# ft232h.net
KiCad netlist of a schematic drawn in Altium Designer
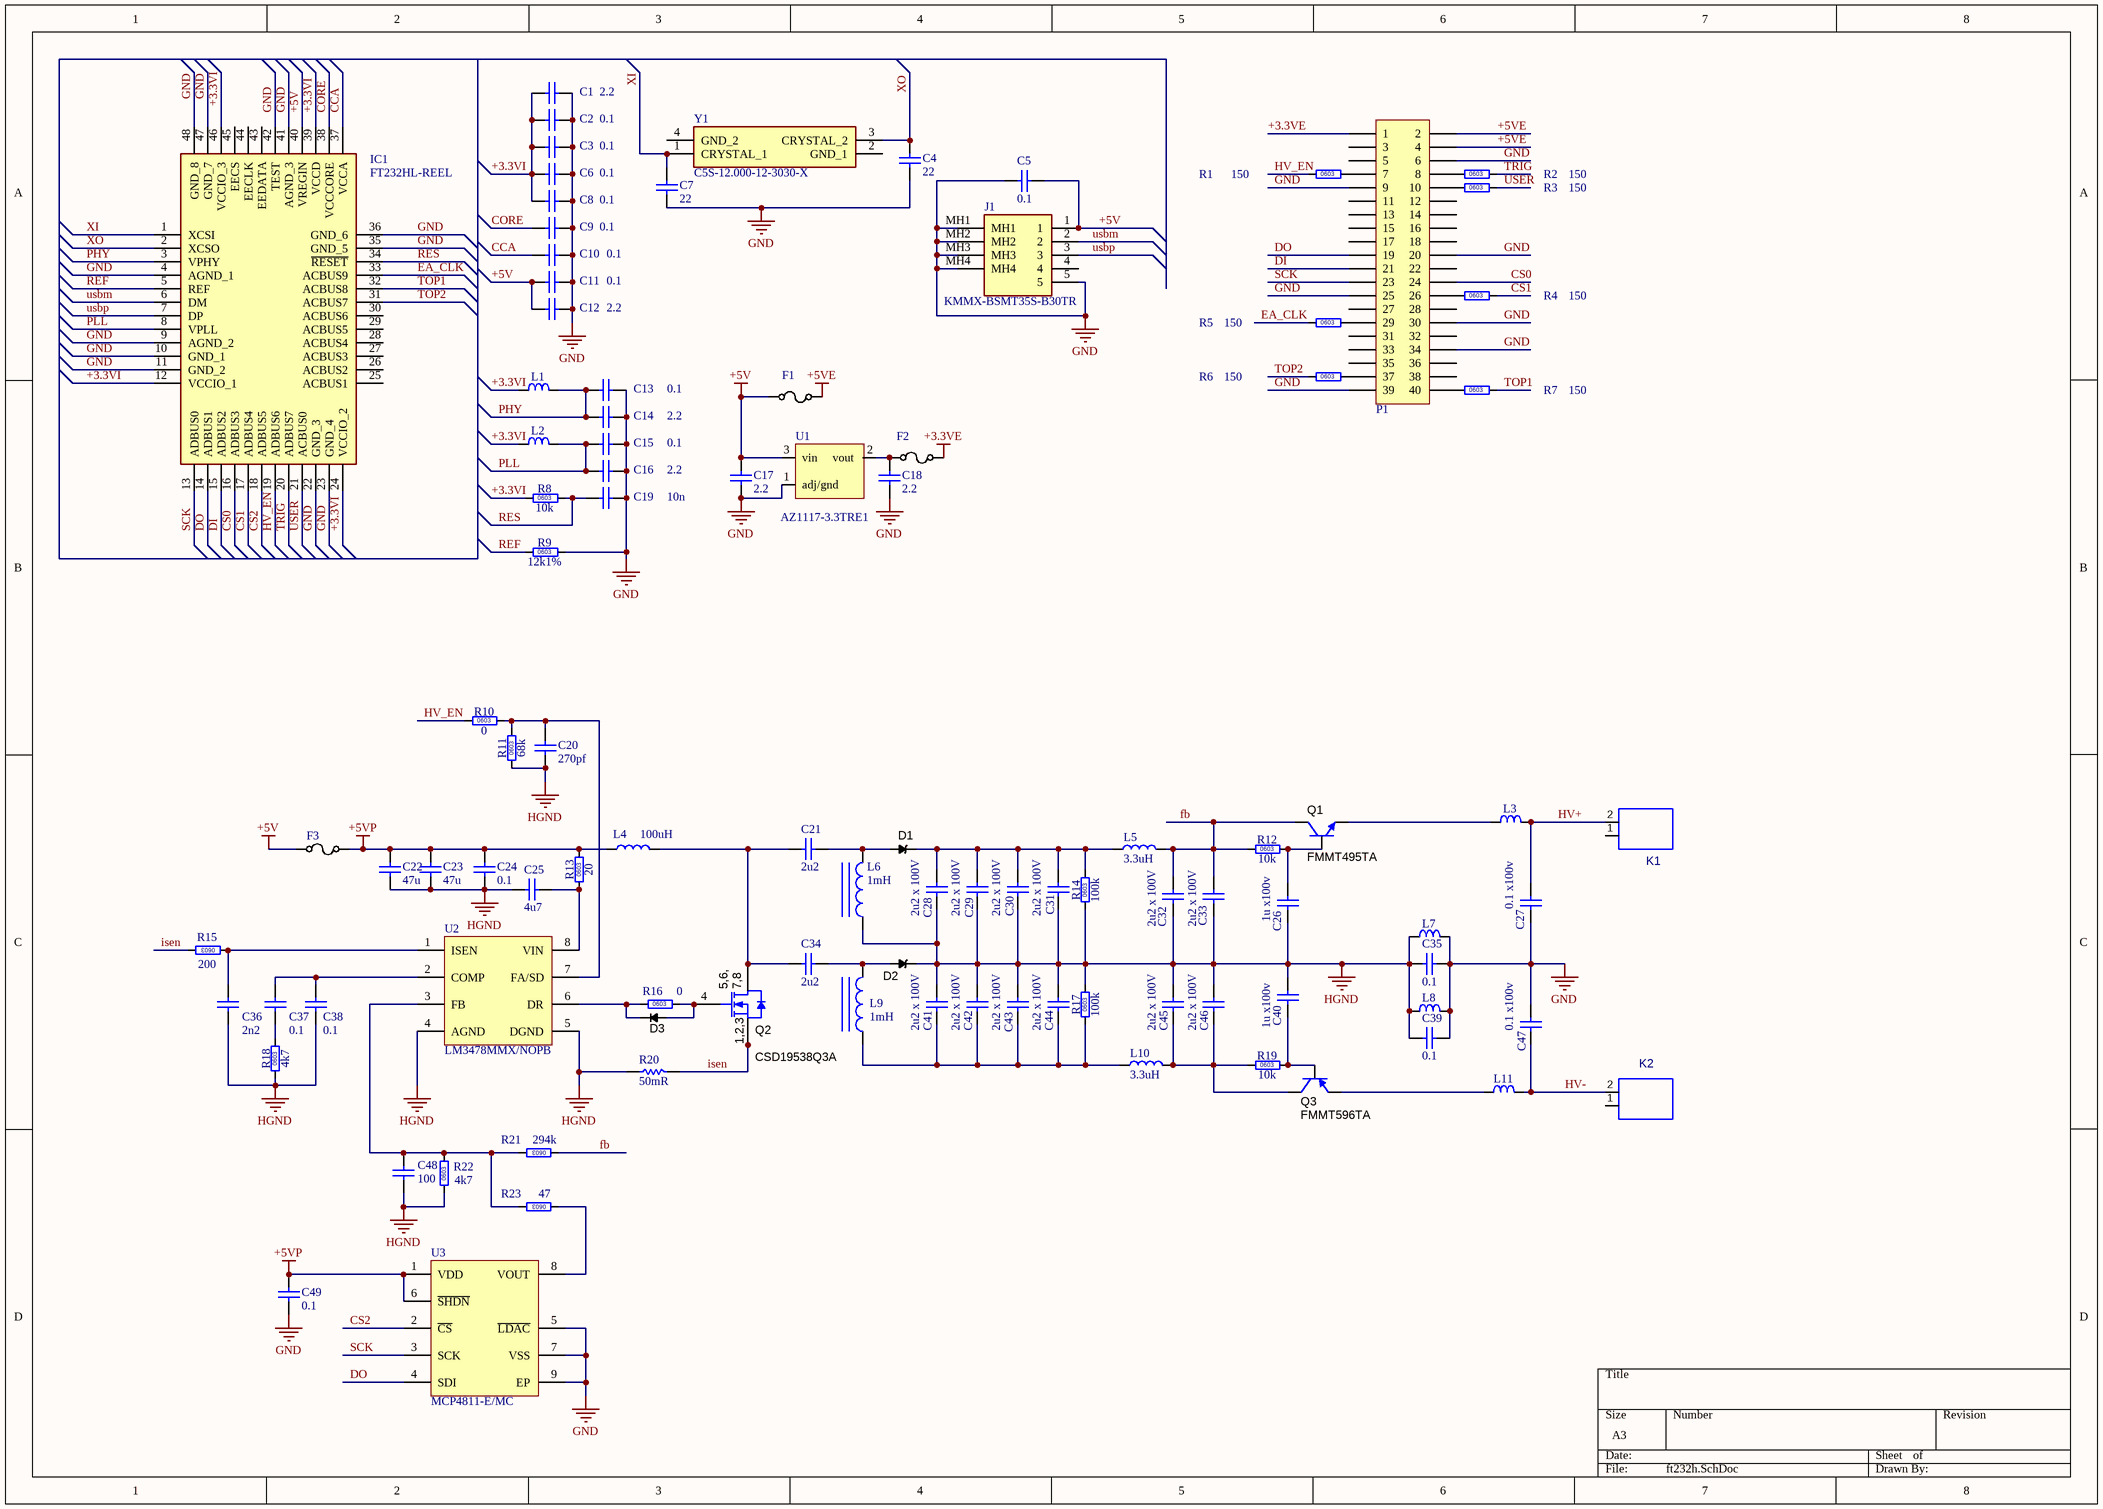
[diagram p0: ft232h.SchDoc]

(export (version "E")
  (design (tool "Eeschema 10.0.6"))
  (components
    (comp (ref "C1")
      (value "2.2")
      (footprint "SM0603 _3D_cap")
      (description "Capacitor  0603 inch")
      (fields (field (name "Comment") "cap0603"))
      (libsource (lib "alt2017") (part "cap0603"))
    )
    (comp (ref "C2")
      (value "0.1")
      (footprint "SM0603 _3D_cap")
      (description "Capacitor  0603 inch")
      (fields (field (name "Comment") "cap0603"))
      (libsource (lib "alt2017") (part "cap0603"))
    )
    (comp (ref "C3")
      (value "0.1")
      (footprint "SM0603 _3D_cap")
      (description "Capacitor  0603 inch")
      (fields (field (name "Comment") "cap0603"))
      (libsource (lib "alt2017") (part "cap0603"))
    )
    (comp (ref "C4")
      (value "22")
      (footprint "SM0603 _3D_cap")
      (description "Capacitor  0603 inch")
      (fields (field (name "Comment") "cap0603"))
      (libsource (lib "alt2017") (part "cap0603"))
    )
    (comp (ref "C5")
      (value "0.1")
      (footprint "SM0603 _3D_cap")
      (description "Capacitor  0603 inch")
      (fields (field (name "Comment") "cap0603"))
      (libsource (lib "alt2017") (part "cap0603"))
    )
    (comp (ref "C6")
      (value "0.1")
      (footprint "SM0603 _3D_cap")
      (description "Capacitor  0603 inch")
      (fields (field (name "Comment") "cap0603"))
      (libsource (lib "alt2017") (part "cap0603"))
    )
    (comp (ref "C7")
      (value "22")
      (footprint "SM0603 _3D_cap")
      (description "Capacitor  0603 inch")
      (fields (field (name "Comment") "cap0603"))
      (libsource (lib "alt2017") (part "cap0603"))
    )
    (comp (ref "C8")
      (value "0.1")
      (footprint "SM0603 _3D_cap")
      (description "Capacitor  0603 inch")
      (fields (field (name "Comment") "cap0603"))
      (libsource (lib "alt2017") (part "cap0603"))
    )
    (comp (ref "C9")
      (value "0.1")
      (footprint "SM0603 _3D_cap")
      (description "Capacitor  0603 inch")
      (fields (field (name "Comment") "cap0603"))
      (libsource (lib "alt2017") (part "cap0603"))
    )
    (comp (ref "C10")
      (value "0.1")
      (footprint "SM0603 _3D_cap")
      (description "Capacitor  0603 inch")
      (fields (field (name "Comment") "cap0603"))
      (libsource (lib "alt2017") (part "cap0603"))
    )
    (comp (ref "C11")
      (value "0.1")
      (footprint "SM0603 _3D_cap")
      (description "Capacitor  0603 inch")
      (fields (field (name "Comment") "cap0603"))
      (libsource (lib "alt2017") (part "cap0603"))
    )
    (comp (ref "C12")
      (value "2.2")
      (footprint "SM0603 _3D_cap")
      (description "Capacitor  0603 inch")
      (fields (field (name "Comment") "cap0603"))
      (libsource (lib "alt2017") (part "cap0603"))
    )
    (comp (ref "C13")
      (value "0.1")
      (footprint "SM0603 _3D_cap")
      (description "Capacitor  0603 inch")
      (fields (field (name "Comment") "cap0603"))
      (libsource (lib "alt2017") (part "cap0603"))
    )
    (comp (ref "C14")
      (value "2.2")
      (footprint "SM0603 _3D_cap")
      (description "Capacitor  0603 inch")
      (fields (field (name "Comment") "cap0603"))
      (libsource (lib "alt2017") (part "cap0603"))
    )
    (comp (ref "C15")
      (value "0.1")
      (footprint "SM0603 _3D_cap")
      (description "Capacitor  0603 inch")
      (fields (field (name "Comment") "cap0603"))
      (libsource (lib "alt2017") (part "cap0603"))
    )
    (comp (ref "C16")
      (value "2.2")
      (footprint "SM0603 _3D_cap")
      (description "Capacitor  0603 inch")
      (fields (field (name "Comment") "cap0603"))
      (libsource (lib "alt2017") (part "cap0603"))
    )
    (comp (ref "C17")
      (value "2.2")
      (footprint "SM0603 _3D_cap")
      (description "Capacitor  0603 inch")
      (fields (field (name "Comment") "cap0603"))
      (libsource (lib "alt2017") (part "cap0603"))
    )
    (comp (ref "C18")
      (value "2.2")
      (footprint "SM0603 _3D_cap")
      (description "Capacitor  0603 inch")
      (fields (field (name "Comment") "cap0603"))
      (libsource (lib "alt2017") (part "cap0603"))
    )
    (comp (ref "C19")
      (value "10n")
      (footprint "SM0603 _3D_cap")
      (description "Capacitor  0603 inch")
      (fields (field (name "Comment") "cap0603"))
      (libsource (lib "alt2017") (part "cap0603"))
    )
    (comp (ref "C20")
      (value "270pf")
      (footprint "SM0603 _3D_cap")
      (description "Capacitor  0603 inch")
      (fields (field (name "Comment") "cap0603"))
      (libsource (lib "alt2017") (part "cap0603"))
    )
    (comp (ref "C21")
      (value "2u2")
      (footprint "SM0603 _3D_cap")
      (description "Capacitor  0603 inch")
      (fields (field (name "Comment") "cap0603"))
      (libsource (lib "alt2017") (part "cap0603"))
    )
    (comp (ref "C22")
      (value "47u")
      (footprint "SM0805")
      (description "Capacitor")
      (fields (field (name "Comment") "cap0805"))
      (libsource (lib "alt2017") (part "cap0805"))
    )
    (comp (ref "C23")
      (value "47u")
      (footprint "SM0805")
      (description "Capacitor")
      (fields (field (name "Comment") "cap0805"))
      (libsource (lib "alt2017") (part "cap0805"))
    )
    (comp (ref "C24")
      (value "0.1")
      (footprint "SM0603 _3D_cap")
      (description "Capacitor  0603 inch")
      (fields (field (name "Comment") "cap0603"))
      (libsource (lib "alt2017") (part "cap0603"))
    )
    (comp (ref "C25")
      (value "4u7")
      (footprint "SM0603 _3D_cap")
      (description "Capacitor  0603 inch")
      (fields (field (name "Comment") "cap0603"))
      (libsource (lib "alt2017") (part "cap0603"))
    )
    (comp (ref "C26")
      (value "1u x100v")
      (footprint "SM0603 _3D_cap")
      (description "Capacitor  0603 inch")
      (fields (field (name "Comment") "cap0603"))
      (libsource (lib "alt2017") (part "cap0603"))
    )
    (comp (ref "C27")
      (value "0.1 x100v")
      (footprint "SM0603 _3D_cap")
      (description "Capacitor  0603 inch")
      (fields (field (name "Comment") "cap0603"))
      (libsource (lib "alt2017") (part "cap0603"))
    )
    (comp (ref "C28")
      (value "2u2 x 100V")
      (footprint "SM1206")
      (description "Capacitor")
      (fields (field (name "Comment") "cap1206"))
      (libsource (lib "alt2017") (part "cap1206"))
    )
    (comp (ref "C29")
      (value "2u2 x 100V")
      (footprint "SM1206")
      (description "Capacitor")
      (fields (field (name "Comment") "cap1206"))
      (libsource (lib "alt2017") (part "cap1206"))
    )
    (comp (ref "C30")
      (value "2u2 x 100V")
      (footprint "SM1206")
      (description "Capacitor")
      (fields (field (name "Comment") "cap1206"))
      (libsource (lib "alt2017") (part "cap1206"))
    )
    (comp (ref "C31")
      (value "2u2 x 100V")
      (footprint "SM1206")
      (description "Capacitor")
      (fields (field (name "Comment") "cap1206"))
      (libsource (lib "alt2017") (part "cap1206"))
    )
    (comp (ref "C32")
      (value "2u2 x 100V")
      (footprint "SM1206")
      (description "Capacitor")
      (fields (field (name "Comment") "cap1206"))
      (libsource (lib "alt2017") (part "cap1206"))
    )
    (comp (ref "C33")
      (value "2u2 x 100V")
      (footprint "SM1206")
      (description "Capacitor")
      (fields (field (name "Comment") "cap1206"))
      (libsource (lib "alt2017") (part "cap1206"))
    )
    (comp (ref "C34")
      (value "2u2")
      (footprint "SM0603 _3D_cap")
      (description "Capacitor  0603 inch")
      (fields (field (name "Comment") "cap0603"))
      (libsource (lib "alt2017") (part "cap0603"))
    )
    (comp (ref "C35")
      (value "0.1")
      (footprint "SM0603 _3D_cap")
      (description "Capacitor  0603 inch")
      (fields (field (name "Comment") "cap0603"))
      (libsource (lib "alt2017") (part "cap0603"))
    )
    (comp (ref "C36")
      (value "2n2")
      (footprint "SM0603 _3D_cap")
      (description "Capacitor  0603 inch")
      (fields (field (name "Comment") "cap0603"))
      (libsource (lib "alt2017") (part "cap0603"))
    )
    (comp (ref "C37")
      (value "0.1")
      (footprint "SM0603 _3D_cap")
      (description "Capacitor  0603 inch")
      (fields (field (name "Comment") "cap0603"))
      (libsource (lib "alt2017") (part "cap0603"))
    )
    (comp (ref "C38")
      (value "0.1")
      (footprint "SM0603 _3D_cap")
      (description "Capacitor  0603 inch")
      (fields (field (name "Comment") "cap0603"))
      (libsource (lib "alt2017") (part "cap0603"))
    )
    (comp (ref "C39")
      (value "0.1")
      (footprint "SM0603 _3D_cap")
      (description "Capacitor  0603 inch")
      (fields (field (name "Comment") "cap0603"))
      (libsource (lib "alt2017") (part "cap0603"))
    )
    (comp (ref "C40")
      (value "1u x100v")
      (footprint "SM0603 _3D_cap")
      (description "Capacitor  0603 inch")
      (fields (field (name "Comment") "cap0603"))
      (libsource (lib "alt2017") (part "cap0603"))
    )
    (comp (ref "C41")
      (value "2u2 x 100V")
      (footprint "SM1206")
      (description "Capacitor")
      (fields (field (name "Comment") "cap1206"))
      (libsource (lib "alt2017") (part "cap1206"))
    )
    (comp (ref "C42")
      (value "2u2 x 100V")
      (footprint "SM1206")
      (description "Capacitor")
      (fields (field (name "Comment") "cap1206"))
      (libsource (lib "alt2017") (part "cap1206"))
    )
    (comp (ref "C43")
      (value "2u2 x 100V")
      (footprint "SM1206")
      (description "Capacitor")
      (fields (field (name "Comment") "cap1206"))
      (libsource (lib "alt2017") (part "cap1206"))
    )
    (comp (ref "C44")
      (value "2u2 x 100V")
      (footprint "SM1206")
      (description "Capacitor")
      (fields (field (name "Comment") "cap1206"))
      (libsource (lib "alt2017") (part "cap1206"))
    )
    (comp (ref "C45")
      (value "2u2 x 100V")
      (footprint "SM1206")
      (description "Capacitor")
      (fields (field (name "Comment") "cap1206"))
      (libsource (lib "alt2017") (part "cap1206"))
    )
    (comp (ref "C46")
      (value "2u2 x 100V")
      (footprint "SM1206")
      (description "Capacitor")
      (fields (field (name "Comment") "cap1206"))
      (libsource (lib "alt2017") (part "cap1206"))
    )
    (comp (ref "C47")
      (value "0.1 x100v")
      (footprint "SM0603 _3D_cap")
      (description "Capacitor  0603 inch")
      (fields (field (name "Comment") "cap0603"))
      (libsource (lib "alt2017") (part "cap0603"))
    )
    (comp (ref "C48")
      (value "100")
      (footprint "SM0603 _3D_cap")
      (description "Capacitor  0603 inch")
      (fields (field (name "Comment") "cap0603"))
      (libsource (lib "alt2017") (part "cap0603"))
    )
    (comp (ref "C49")
      (value "0.1")
      (footprint "SM0603 _3D_cap")
      (description "Capacitor  0603 inch")
      (fields (field (name "Comment") "cap0603"))
      (libsource (lib "alt2017") (part "cap0603"))
    )
    (comp (ref "D1")
      (value "STPS1150A")
      (footprint "SMA")
      (description "DIODE SCHOTTKY 150V 1A SMA")
      (fields (field (name "MANUFACTURER") "STMicroelectronics"))
      (libsource (lib "alt2017") (part "STPS1150A"))
    )
    (comp (ref "D2")
      (value "STPS1150A")
      (footprint "SMA")
      (description "DIODE SCHOTTKY 150V 1A SMA")
      (fields (field (name "MANUFACTURER") "STMicroelectronics"))
      (libsource (lib "alt2017") (part "STPS1150A"))
    )
    (comp (ref "D3")
      (value "1N4148X-TP")
      (footprint "SOD-523")
      (description "DIODE SWITCHING 75V 0.3A SOD-523")
      (fields (field (name "MANUFACTURER") "Micro Commercial Components"))
      (libsource (lib "alt2017") (part "1N4148X-TP"))
    )
    (comp (ref "F1")
      (value "Fuse_0805")
      (footprint "MF-PSMF050X-2")
      (description "FUSE 0805 RESETTABLE PTC 6V 500MA")
      (fields
        (field (name "MANUFACTURER") "BOURNS")
        (field (name "MANUFACTURER PART NUMBER") "MF-PSMF050X-2")
      )
      (libsource (lib "alt2017") (part "Fuse_0805"))
    )
    (comp (ref "F2")
      (value "Fuse_0805")
      (footprint "MF-PSMF050X-2")
      (description "FUSE 0805 RESETTABLE PTC 6V 500MA")
      (fields
        (field (name "MANUFACTURER") "BOURNS")
        (field (name "MANUFACTURER PART NUMBER") "MF-PSMF050X-2")
      )
      (libsource (lib "alt2017") (part "Fuse_0805"))
    )
    (comp (ref "F3")
      (value "Fuse_0805")
      (footprint "MF-PSMF050X-2")
      (description "FUSE 0805 RESETTABLE PTC 6V 500MA")
      (fields
        (field (name "MANUFACTURER") "BOURNS")
        (field (name "MANUFACTURER PART NUMBER") "MF-PSMF050X-2")
      )
      (libsource (lib "alt2017") (part "Fuse_0805"))
    )
    (comp (ref "IC1")
      (value "FT232HL-REEL")
      (footprint "SamacSys:QFP50P900X900X160-48N")
      (description "Integrated Circuit")
      (fields (field (name "MOUSER PART NUMBER") "895-FT232HL-REEL"))
      (libsource (lib "*") (part "FT232HL-REEL"))
    )
    (comp (ref "J1")
      (value "KMMX-BSMT35S-B30TR")
      (footprint "SamacSys:KMMXBSMT35SB30TR")
      (description "Connector")
      (libsource (lib "*") (part "KMMX-BSMT35S-B30TR"))
    )
    (comp (ref "K1") (value "1x2PLS") (footprint "JUMPER2") (libsource (lib "alt2017") (part "1x2PLS")))
    (comp (ref "K2") (value "1x2PLS") (footprint "JUMPER2") (libsource (lib "alt2017") (part "1x2PLS")))
    (comp (ref "L1")
      (value "75R@100MHz")
      (footprint "SM0603_3D_res")
      (description "chip inductance 0603")
      (fields (field (name "PART NUMBER") "IND0805_MURATA_BLM21BB750SN1D") (field (name "POWER") "700mA"))
      (libsource (lib "alt_vovan") (part "chip inductance 0603"))
    )
    (comp (ref "L2")
      (value "75R@100MHz")
      (footprint "SM0603_3D_res")
      (description "chip inductance 0603")
      (fields (field (name "PART NUMBER") "IND0805_MURATA_BLM21BB750SN1D") (field (name "POWER") "700mA"))
      (libsource (lib "alt_vovan") (part "chip inductance 0603"))
    )
    (comp (ref "L3")
      (value "75R@100MHz")
      (footprint "SM0603_3D_res")
      (description "chip inductance 0603")
      (fields (field (name "PART NUMBER") "IND0805_MURATA_BLM21BB750SN1D") (field (name "POWER") "700mA"))
      (libsource (lib "alt_vovan") (part "chip inductance 0603"))
    )
    (comp (ref "L4")
      (value "100uH")
      (footprint "WE-LQS_8040")
      (description "INDUCTOR 100uH 8040 1A 290mOhm")
      (fields
        (field (name "MANUFACTURER") "Wurth Electronics")
        (field (name "MANUFACTURER PART NUMBER") "74404084101")
      )
      (libsource (lib "alt2017") (part "inductance_8040"))
    )
    (comp (ref "L5")
      (value "3.3uH")
      (footprint "WE 74479775233")
      (description "INDUCTOR 3.3uH 0805 ±20%  1A")
      (fields
        (field (name "MANUFACTURER") "Wurth Electronics")
        (field (name "MANUFACTURER PART NUMBER") "74479775233")
      )
      (libsource (lib "alt2017") (part "Inductor_0805"))
    )
    (comp (ref "L6")
      (value "1mH")
      (footprint "WE-TPC_4828")
      (description "INDUCTOR 1mH ±30% 140mA")
      (fields
        (field (name "MANUFACTURER") "Wurth Electronics")
        (field (name "MANUFACTURER PART NUMBER") "744043102")
      )
      (libsource (lib "alt2017") (part "inductor_4828"))
    )
    (comp (ref "L7")
      (value "75R@100MHz")
      (footprint "SM0603_3D_res")
      (description "chip inductance 0603")
      (fields (field (name "PART NUMBER") "IND0805_MURATA_BLM21BB750SN1D") (field (name "POWER") "700mA"))
      (libsource (lib "alt_vovan") (part "chip inductance 0603"))
    )
    (comp (ref "L8")
      (value "75R@100MHz")
      (footprint "SM0603_3D_res")
      (description "chip inductance 0603")
      (fields (field (name "PART NUMBER") "IND0805_MURATA_BLM21BB750SN1D") (field (name "POWER") "700mA"))
      (libsource (lib "alt_vovan") (part "chip inductance 0603"))
    )
    (comp (ref "L9")
      (value "1mH")
      (footprint "WE-TPC_4828")
      (description "INDUCTOR 1mH ±30% 140mA")
      (fields
        (field (name "MANUFACTURER") "Wurth Electronics")
        (field (name "MANUFACTURER PART NUMBER") "744043102")
      )
      (libsource (lib "alt2017") (part "inductor_4828"))
    )
    (comp (ref "L10")
      (value "3.3uH")
      (footprint "WE 74479775233")
      (description "INDUCTOR 3.3uH 0805 ±20%  1A")
      (fields
        (field (name "MANUFACTURER") "Wurth Electronics")
        (field (name "MANUFACTURER PART NUMBER") "74479775233")
      )
      (libsource (lib "alt2017") (part "Inductor_0805"))
    )
    (comp (ref "L11")
      (value "75R@100MHz")
      (footprint "SM0603_3D_res")
      (description "chip inductance 0603")
      (fields (field (name "PART NUMBER") "IND0805_MURATA_BLM21BB750SN1D") (field (name "POWER") "700mA"))
      (libsource (lib "alt_vovan") (part "chip inductance 0603"))
    )
    (comp (ref "P1")
      (value "2x20 2.54mm vertical")
      (footprint "PLD-40")
      (description "Header, 40-Pin")
      (libsource (lib "alt2017") (part "2x20 2.54mm vertical"))
    )
    (comp (ref "Q1")
      (value "FMMT495TA")
      (footprint "SOT-23-3")
      (description "TRANSISTOR NPN 150V 1A AEC-Q101 SOT-23")
      (fields (field (name "MANUFACTURER") "Diodes Inc."))
      (libsource (lib "alt2017") (part "FMMT495TA"))
    )
    (comp (ref "Q2")
      (value "CSD19538Q3A")
      (footprint "DNH0008A")
      (description "MOSFET N 100V 5A")
      (fields (field (name "MANUFACTURER") "Texas Instruments"))
      (libsource (lib "alt2017") (part "CSD19538Q3A"))
    )
    (comp (ref "Q3")
      (value "FMMT596TA")
      (footprint "SOT-23-3")
      (description "TRANSISTOR PNP 200V 0.3A SOT-23")
      (fields (field (name "MANUFACTURER") "Diodes Inc."))
      (libsource (lib "alt2017") (part "FMMT596TA"))
    )
    (comp (ref "R1")
      (value "150")
      (footprint "SM0603_3D_res")
      (description "Res_0603_EU")
      (fields (field (name "PART NUMBER") "R1206_4K7_1%_0.25W_100PPM") (field (name "POWER") "0.25W"))
      (libsource (lib "alt_vovan") (part "Res_0603_EU"))
    )
    (comp (ref "R2")
      (value "150")
      (footprint "SM0603_3D_res")
      (description "Res_0603_EU")
      (fields (field (name "PART NUMBER") "R1206_4K7_1%_0.25W_100PPM") (field (name "POWER") "0.25W"))
      (libsource (lib "alt_vovan") (part "Res_0603_EU"))
    )
    (comp (ref "R3")
      (value "150")
      (footprint "SM0603_3D_res")
      (description "Res_0603_EU")
      (fields (field (name "PART NUMBER") "R1206_4K7_1%_0.25W_100PPM") (field (name "POWER") "0.25W"))
      (libsource (lib "alt_vovan") (part "Res_0603_EU"))
    )
    (comp (ref "R4")
      (value "150")
      (footprint "SM0603_3D_res")
      (description "Res_0603_EU")
      (fields (field (name "PART NUMBER") "R1206_4K7_1%_0.25W_100PPM") (field (name "POWER") "0.25W"))
      (libsource (lib "alt_vovan") (part "Res_0603_EU"))
    )
    (comp (ref "R5")
      (value "150")
      (footprint "SM0603_3D_res")
      (description "Res_0603_EU")
      (fields (field (name "PART NUMBER") "R1206_4K7_1%_0.25W_100PPM") (field (name "POWER") "0.25W"))
      (libsource (lib "alt_vovan") (part "Res_0603_EU"))
    )
    (comp (ref "R6")
      (value "150")
      (footprint "SM0603_3D_res")
      (description "Res_0603_EU")
      (fields (field (name "PART NUMBER") "R1206_4K7_1%_0.25W_100PPM") (field (name "POWER") "0.25W"))
      (libsource (lib "alt_vovan") (part "Res_0603_EU"))
    )
    (comp (ref "R7")
      (value "150")
      (footprint "SM0603_3D_res")
      (description "Res_0603_EU")
      (fields (field (name "PART NUMBER") "R1206_4K7_1%_0.25W_100PPM") (field (name "POWER") "0.25W"))
      (libsource (lib "alt_vovan") (part "Res_0603_EU"))
    )
    (comp (ref "R8")
      (value "10k")
      (footprint "SM0603_3D_res")
      (description "Res_0603_EU")
      (fields (field (name "PART NUMBER") "R1206_4K7_1%_0.25W_100PPM") (field (name "POWER") "0.25W"))
      (libsource (lib "alt_vovan") (part "Res_0603_EU"))
    )
    (comp (ref "R9")
      (value "12k1%")
      (footprint "SM0603_3D_res")
      (description "Res_0603_EU")
      (fields (field (name "PART NUMBER") "R1206_4K7_1%_0.25W_100PPM") (field (name "POWER") "0.25W"))
      (libsource (lib "alt_vovan") (part "Res_0603_EU"))
    )
    (comp (ref "R10")
      (value "0")
      (footprint "SM0603_3D_res")
      (description "Res_0603_EU")
      (fields (field (name "PART NUMBER") "R1206_4K7_1%_0.25W_100PPM") (field (name "POWER") "0.25W"))
      (libsource (lib "alt_vovan") (part "Res_0603_EU"))
    )
    (comp (ref "R11")
      (value "68k")
      (footprint "SM0603_3D_res")
      (description "Res_0603_EU")
      (fields (field (name "PART NUMBER") "R1206_4K7_1%_0.25W_100PPM") (field (name "POWER") "0.25W"))
      (libsource (lib "alt_vovan") (part "Res_0603_EU"))
    )
    (comp (ref "R12")
      (value "10k")
      (footprint "SM0603_3D_res")
      (description "Res_0603_EU")
      (fields (field (name "PART NUMBER") "R1206_4K7_1%_0.25W_100PPM") (field (name "POWER") "0.25W"))
      (libsource (lib "alt_vovan") (part "Res_0603_EU"))
    )
    (comp (ref "R13")
      (value "20")
      (footprint "SM0603_3D_res")
      (description "Res_0603_EU")
      (fields (field (name "PART NUMBER") "R1206_4K7_1%_0.25W_100PPM") (field (name "POWER") "0.25W"))
      (libsource (lib "alt_vovan") (part "Res_0603_EU"))
    )
    (comp (ref "R14")
      (value "100k")
      (footprint "SM0603_3D_res")
      (description "Res_0603_EU")
      (fields (field (name "PART NUMBER") "R1206_4K7_1%_0.25W_100PPM") (field (name "POWER") "0.25W"))
      (libsource (lib "alt_vovan") (part "Res_0603_EU"))
    )
    (comp (ref "R15")
      (value "200")
      (footprint "SM0603_3D_res")
      (description "Res_0603_EU")
      (fields (field (name "PART NUMBER") "R1206_4K7_1%_0.25W_100PPM") (field (name "POWER") "0.25W"))
      (libsource (lib "alt_vovan") (part "Res_0603_EU"))
    )
    (comp (ref "R16")
      (value "0")
      (footprint "SM0603_3D_res")
      (description "Res_0603_EU")
      (fields (field (name "PART NUMBER") "R1206_4K7_1%_0.25W_100PPM") (field (name "POWER") "0.25W"))
      (libsource (lib "alt_vovan") (part "Res_0603_EU"))
    )
    (comp (ref "R17")
      (value "100k")
      (footprint "SM0603_3D_res")
      (description "Res_0603_EU")
      (fields (field (name "PART NUMBER") "R1206_4K7_1%_0.25W_100PPM") (field (name "POWER") "0.25W"))
      (libsource (lib "alt_vovan") (part "Res_0603_EU"))
    )
    (comp (ref "R18")
      (value "4k7")
      (footprint "SM0603_3D_res")
      (description "Res_0603_EU")
      (fields (field (name "PART NUMBER") "R1206_4K7_1%_0.25W_100PPM") (field (name "POWER") "0.25W"))
      (libsource (lib "alt_vovan") (part "Res_0603_EU"))
    )
    (comp (ref "R19")
      (value "10k")
      (footprint "SM0603_3D_res")
      (description "Res_0603_EU")
      (fields (field (name "PART NUMBER") "R1206_4K7_1%_0.25W_100PPM") (field (name "POWER") "0.25W"))
      (libsource (lib "alt_vovan") (part "Res_0603_EU"))
    )
    (comp (ref "R20")
      (value "50mR")
      (footprint "RES 2010/5025")
      (description "RESISTOR 0.05R 2010 1%")
      (fields
        (field (name "MANUFACTURER") "Panasonic")
        (field (name "MANUFACTURER PART NUMBER") "ERJ-L1DKF50MU")
      )
      (libsource (lib "alt2017") (part "Res_SMT_2010"))
    )
    (comp (ref "R21")
      (value "294k")
      (footprint "SM0603_3D_res")
      (description "Res_0603_EU")
      (fields (field (name "PART NUMBER") "R1206_4K7_1%_0.25W_100PPM") (field (name "POWER") "0.25W"))
      (libsource (lib "alt_vovan") (part "Res_0603_EU"))
    )
    (comp (ref "R22")
      (value "4k7")
      (footprint "SM0603_3D_res")
      (description "Res_0603_EU")
      (fields (field (name "PART NUMBER") "R1206_4K7_1%_0.25W_100PPM") (field (name "POWER") "0.25W"))
      (libsource (lib "alt_vovan") (part "Res_0603_EU"))
    )
    (comp (ref "R23")
      (value "47")
      (footprint "SM0603_3D_res")
      (description "Res_0603_EU")
      (fields (field (name "PART NUMBER") "R1206_4K7_1%_0.25W_100PPM") (field (name "POWER") "0.25W"))
      (libsource (lib "alt_vovan") (part "Res_0603_EU"))
    )
    (comp (ref "U1")
      (value "ldo")
      (footprint "SOT89-150P409X160-3N")
      (description "SOT89-3 ldo")
      (fields (field (name "ALTIUM_UNNAMED_1") "AZ1117-3.3TRE1"))
      (libsource (lib "alt2017") (part "LM1117-XX-SOT89-3"))
    )
    (comp (ref "U2")
      (value "LM3478MMX/NOPB")
      (footprint "MSOP8")
      (description "DC/DC Controller 2.97V to 40V Input")
      (fields (field (name "MANUFACTURER") "TI National Semiconductor"))
      (libsource (lib "alt_vovan") (part "LM3478MMX/NOPB"))
    )
    (comp (ref "U3")
      (value "MCP4811-E/MC")
      (footprint "DFN-8")
      (description "DAC 1-CH 10-bit DFN-8")
      (fields (field (name "MANUFACTURER") "Microchip"))
      (libsource (lib "alt2017") (part "MCP4811-E/MC"))
    )
    (comp (ref "Y1")
      (value "C5S-12.000-12-3030-X")
      (footprint "SamacSys:C5S")
      (description "Crystal or Oscillator")
      (libsource (lib "*") (part "C5S-12.000-12-3030-X"))
    )
  )
  (nets
    (net (code "1") (name "+3.3VE") (class "Default")
      (node (ref "F2") (pin "2") (pinfunction "2_2") (pintype "passive"))
      (node (ref "P1") (pin "1") (pinfunction "1_1") (pintype "passive"))
    )
    (net (code "2") (name "+5V") (class "Default")
      (node (ref "C11") (pin "2") (pinfunction "2_2") (pintype "passive"))
      (node (ref "C12") (pin "2") (pinfunction "2_2") (pintype "passive"))
      (node (ref "C17") (pin "2") (pinfunction "2_2") (pintype "passive"))
      (node (ref "C5") (pin "1") (pinfunction "1_1") (pintype "passive"))
      (node (ref "F1") (pin "1") (pinfunction "1_1") (pintype "passive"))
      (node (ref "F3") (pin "1") (pinfunction "1_1") (pintype "passive"))
      (node (ref "IC1") (pin "40") (pinfunction "VREGIN_40") (pintype "passive"))
      (node (ref "J1") (pin "1") (pinfunction "1_1") (pintype "passive"))
      (node (ref "U1") (pin "3") (pinfunction "vin_3") (pintype "passive"))
    )
    (net (code "3") (name "+5VE") (class "Default")
      (node (ref "F1") (pin "2") (pinfunction "2_2") (pintype "passive"))
      (node (ref "P1") (pin "2") (pinfunction "2_2") (pintype "passive"))
      (node (ref "P1") (pin "4") (pinfunction "4_4") (pintype "passive"))
    )
    (net (code "4") (name "+5VP") (class "Default")
      (node (ref "C22") (pin "2") (pinfunction "2_2") (pintype "passive"))
      (node (ref "C23") (pin "2") (pinfunction "2_2") (pintype "passive"))
      (node (ref "C24") (pin "2") (pinfunction "2_2") (pintype "passive"))
      (node (ref "C49") (pin "1") (pinfunction "1_1") (pintype "passive"))
      (node (ref "F3") (pin "2") (pinfunction "2_2") (pintype "passive"))
      (node (ref "L4") (pin "1") (pinfunction "1_1") (pintype "passive"))
      (node (ref "R13") (pin "2") (pinfunction "2_2") (pintype "passive"))
      (node (ref "U3") (pin "1") (pinfunction "VDD_1") (pintype "passive"))
      (node (ref "U3") (pin "6") (pinfunction "~{SHDN}_6") (pintype "passive"))
    )
    (net (code "5") (name "/+3.3VI") (class "Default")
      (node (ref "C1") (pin "2") (pinfunction "2_2") (pintype "passive"))
      (node (ref "C2") (pin "2") (pinfunction "2_2") (pintype "passive"))
      (node (ref "C3") (pin "2") (pinfunction "2_2") (pintype "passive"))
      (node (ref "C6") (pin "2") (pinfunction "2_2") (pintype "passive"))
      (node (ref "C8") (pin "2") (pinfunction "2_2") (pintype "passive"))
      (node (ref "IC1") (pin "12") (pinfunction "VCCIO_1_12") (pintype "passive"))
      (node (ref "IC1") (pin "24") (pinfunction "VCCIO_2_24") (pintype "passive"))
      (node (ref "IC1") (pin "39") (pinfunction "VCCD_39") (pintype "passive"))
      (node (ref "IC1") (pin "46") (pinfunction "VCCIO_3_46") (pintype "passive"))
      (node (ref "L1") (pin "1") (pinfunction "1_1") (pintype "passive"))
      (node (ref "L2") (pin "1") (pinfunction "1_1") (pintype "passive"))
      (node (ref "R8") (pin "1") (pinfunction "1_1") (pintype "passive"))
    )
    (net (code "6") (name "/CCA") (class "Default")
      (node (ref "C10") (pin "2") (pinfunction "2_2") (pintype "passive"))
      (node (ref "IC1") (pin "37") (pinfunction "VCCA_37") (pintype "passive"))
    )
    (net (code "7") (name "/CORE") (class "Default")
      (node (ref "C9") (pin "2") (pinfunction "2_2") (pintype "passive"))
      (node (ref "IC1") (pin "38") (pinfunction "VCCCORE_38") (pintype "passive"))
    )
    (net (code "8") (name "/CS0") (class "Default")
      (node (ref "IC1") (pin "16") (pinfunction "ADBUS3_16") (pintype "passive"))
      (node (ref "P1") (pin "24") (pinfunction "24_24") (pintype "passive"))
    )
    (net (code "9") (name "/CS1") (class "Default")
      (node (ref "IC1") (pin "17") (pinfunction "ADBUS4_17") (pintype "passive"))
      (node (ref "R4") (pin "2") (pinfunction "2_2") (pintype "passive"))
    )
    (net (code "10") (name "/CS2") (class "Default")
      (node (ref "IC1") (pin "18") (pinfunction "ADBUS5_18") (pintype "passive"))
      (node (ref "U3") (pin "2") (pinfunction "~{CS}_2") (pintype "passive"))
    )
    (net (code "11") (name "/DI") (class "Default")
      (node (ref "IC1") (pin "15") (pinfunction "ADBUS2_15") (pintype "passive"))
      (node (ref "P1") (pin "21") (pinfunction "21_21") (pintype "passive"))
    )
    (net (code "12") (name "/DO") (class "Default")
      (node (ref "IC1") (pin "14") (pinfunction "ADBUS1_14") (pintype "passive"))
      (node (ref "P1") (pin "19") (pinfunction "19_19") (pintype "passive"))
      (node (ref "U3") (pin "4") (pinfunction "SDI_4") (pintype "passive"))
    )
    (net (code "13") (name "/EA_CLK") (class "Default")
      (node (ref "IC1") (pin "33") (pinfunction "ACBUS9_33") (pintype "passive"))
      (node (ref "R5") (pin "1") (pinfunction "1_1") (pintype "passive"))
    )
    (net (code "14") (name "/HV+") (class "Default")
      (node (ref "C27") (pin "2") (pinfunction "2_2") (pintype "passive"))
      (node (ref "K1") (pin "2") (pinfunction "2_2") (pintype "passive"))
      (node (ref "L3") (pin "2") (pinfunction "2_2") (pintype "passive"))
    )
    (net (code "15") (name "/HV-") (class "Default")
      (node (ref "C47") (pin "1") (pinfunction "1_1") (pintype "passive"))
      (node (ref "K2") (pin "2") (pinfunction "2_2") (pintype "passive"))
      (node (ref "L11") (pin "2") (pinfunction "2_2") (pintype "passive"))
    )
    (net (code "16") (name "/HV_EN") (class "Default")
      (node (ref "IC1") (pin "19") (pinfunction "ADBUS6_19") (pintype "passive"))
      (node (ref "R1") (pin "1") (pinfunction "1_1") (pintype "passive"))
      (node (ref "R10") (pin "1") (pinfunction "1_1") (pintype "passive"))
    )
    (net (code "17") (name "/PHY") (class "Default")
      (node (ref "C13") (pin "2") (pinfunction "2_2") (pintype "passive"))
      (node (ref "C14") (pin "2") (pinfunction "2_2") (pintype "passive"))
      (node (ref "IC1") (pin "3") (pinfunction "VPHY_3") (pintype "passive"))
      (node (ref "L1") (pin "2") (pinfunction "2_2") (pintype "passive"))
    )
    (net (code "18") (name "/PLL") (class "Default")
      (node (ref "C15") (pin "2") (pinfunction "2_2") (pintype "passive"))
      (node (ref "C16") (pin "2") (pinfunction "2_2") (pintype "passive"))
      (node (ref "IC1") (pin "8") (pinfunction "VPLL_8") (pintype "passive"))
      (node (ref "L2") (pin "2") (pinfunction "2_2") (pintype "passive"))
    )
    (net (code "19") (name "/REF") (class "Default")
      (node (ref "IC1") (pin "5") (pinfunction "REF_5") (pintype "passive"))
      (node (ref "R9") (pin "1") (pinfunction "1_1") (pintype "passive"))
    )
    (net (code "20") (name "/RES") (class "Default")
      (node (ref "C19") (pin "2") (pinfunction "2_2") (pintype "passive"))
      (node (ref "IC1") (pin "34") (pinfunction "~{RESET}_34") (pintype "passive"))
      (node (ref "R8") (pin "2") (pinfunction "2_2") (pintype "passive"))
    )
    (net (code "21") (name "/SCK") (class "Default")
      (node (ref "IC1") (pin "13") (pinfunction "ADBUS0_13") (pintype "passive"))
      (node (ref "P1") (pin "23") (pinfunction "23_23") (pintype "passive"))
      (node (ref "U3") (pin "3") (pinfunction "SCK_3") (pintype "passive"))
    )
    (net (code "22") (name "/TOP1") (class "Default")
      (node (ref "IC1") (pin "32") (pinfunction "ACBUS8_32") (pintype "passive"))
      (node (ref "R7") (pin "2") (pinfunction "2_2") (pintype "passive"))
    )
    (net (code "23") (name "/TOP2") (class "Default")
      (node (ref "IC1") (pin "31") (pinfunction "ACBUS7_31") (pintype "passive"))
      (node (ref "R6") (pin "1") (pinfunction "1_1") (pintype "passive"))
    )
    (net (code "24") (name "/TRIG") (class "Default")
      (node (ref "IC1") (pin "20") (pinfunction "ADBUS7_20") (pintype "passive"))
      (node (ref "R2") (pin "2") (pinfunction "2_2") (pintype "passive"))
    )
    (net (code "25") (name "/USER") (class "Default")
      (node (ref "IC1") (pin "21") (pinfunction "ACBUS0_21") (pintype "passive"))
      (node (ref "R3") (pin "2") (pinfunction "2_2") (pintype "passive"))
    )
    (net (code "26") (name "/XI") (class "Default")
      (node (ref "C7") (pin "2") (pinfunction "2_2") (pintype "passive"))
      (node (ref "IC1") (pin "1") (pinfunction "XCSI_1") (pintype "passive"))
      (node (ref "Y1") (pin "1") (pinfunction "CRYSTAL_1_1") (pintype "passive"))
    )
    (net (code "27") (name "/XO") (class "Default")
      (node (ref "C4") (pin "2") (pinfunction "2_2") (pintype "passive"))
      (node (ref "IC1") (pin "2") (pinfunction "XCSO_2") (pintype "passive"))
      (node (ref "Y1") (pin "3") (pinfunction "CRYSTAL_2_3") (pintype "passive"))
    )
    (net (code "28") (name "/fb") (class "Default")
      (node (ref "C32") (pin "2") (pinfunction "2_2") (pintype "passive"))
      (node (ref "C33") (pin "2") (pinfunction "2_2") (pintype "passive"))
      (node (ref "L5") (pin "2") (pinfunction "2_2") (pintype "passive"))
      (node (ref "Q1") (pin "3") (pinfunction "C_3") (pintype "passive"))
      (node (ref "R12") (pin "1") (pinfunction "1_1") (pintype "passive"))
      (node (ref "R21") (pin "1") (pinfunction "1_1") (pintype "passive"))
    )
    (net (code "29") (name "/isen") (class "Default")
      (node (ref "Q2") (pin "1") (pinfunction "S_1") (pintype "passive"))
      (node (ref "Q2") (pin "2") (pinfunction "S_2") (pintype "passive"))
      (node (ref "Q2") (pin "3") (pinfunction "S_3") (pintype "passive"))
      (node (ref "R15") (pin "2") (pinfunction "2_2") (pintype "passive"))
      (node (ref "R20") (pin "2") (pintype "passive"))
    )
    (net (code "30") (name "/usbm") (class "Default")
      (node (ref "IC1") (pin "6") (pinfunction "DM_6") (pintype "passive"))
      (node (ref "J1") (pin "2") (pinfunction "2_2") (pintype "passive"))
    )
    (net (code "31") (name "/usbp") (class "Default")
      (node (ref "IC1") (pin "7") (pinfunction "DP_7") (pintype "passive"))
      (node (ref "J1") (pin "3") (pinfunction "3_3") (pintype "passive"))
    )
    (net (code "32") (name "GND") (class "Default")
      (node (ref "C1") (pin "1") (pinfunction "1_1") (pintype "passive"))
      (node (ref "C10") (pin "1") (pinfunction "1_1") (pintype "passive"))
      (node (ref "C11") (pin "1") (pinfunction "1_1") (pintype "passive"))
      (node (ref "C12") (pin "1") (pinfunction "1_1") (pintype "passive"))
      (node (ref "C13") (pin "1") (pinfunction "1_1") (pintype "passive"))
      (node (ref "C14") (pin "1") (pinfunction "1_1") (pintype "passive"))
      (node (ref "C15") (pin "1") (pinfunction "1_1") (pintype "passive"))
      (node (ref "C16") (pin "1") (pinfunction "1_1") (pintype "passive"))
      (node (ref "C17") (pin "1") (pinfunction "1_1") (pintype "passive"))
      (node (ref "C18") (pin "1") (pinfunction "1_1") (pintype "passive"))
      (node (ref "C19") (pin "1") (pinfunction "1_1") (pintype "passive"))
      (node (ref "C2") (pin "1") (pinfunction "1_1") (pintype "passive"))
      (node (ref "C27") (pin "1") (pinfunction "1_1") (pintype "passive"))
      (node (ref "C3") (pin "1") (pinfunction "1_1") (pintype "passive"))
      (node (ref "C35") (pin "2") (pinfunction "2_2") (pintype "passive"))
      (node (ref "C39") (pin "2") (pinfunction "2_2") (pintype "passive"))
      (node (ref "C4") (pin "1") (pinfunction "1_1") (pintype "passive"))
      (node (ref "C47") (pin "2") (pinfunction "2_2") (pintype "passive"))
      (node (ref "C49") (pin "2") (pinfunction "2_2") (pintype "passive"))
      (node (ref "C5") (pin "2") (pinfunction "2_2") (pintype "passive"))
      (node (ref "C6") (pin "1") (pinfunction "1_1") (pintype "passive"))
      (node (ref "C7") (pin "1") (pinfunction "1_1") (pintype "passive"))
      (node (ref "C8") (pin "1") (pinfunction "1_1") (pintype "passive"))
      (node (ref "C9") (pin "1") (pinfunction "1_1") (pintype "passive"))
      (node (ref "IC1") (pin "10") (pinfunction "GND_1_10") (pintype "passive"))
      (node (ref "IC1") (pin "11") (pinfunction "GND_2_11") (pintype "passive"))
      (node (ref "IC1") (pin "22") (pinfunction "GND_3_22") (pintype "passive"))
      (node (ref "IC1") (pin "23") (pinfunction "GND_4_23") (pintype "passive"))
      (node (ref "IC1") (pin "35") (pinfunction "GND_5_35") (pintype "passive"))
      (node (ref "IC1") (pin "36") (pinfunction "GND_6_36") (pintype "passive"))
      (node (ref "IC1") (pin "4") (pinfunction "AGND_1_4") (pintype "passive"))
      (node (ref "IC1") (pin "41") (pinfunction "AGND_3_41") (pintype "passive"))
      (node (ref "IC1") (pin "42") (pinfunction "TEST_42") (pintype "passive"))
      (node (ref "IC1") (pin "47") (pinfunction "GND_7_47") (pintype "passive"))
      (node (ref "IC1") (pin "48") (pinfunction "GND_8_48") (pintype "passive"))
      (node (ref "IC1") (pin "9") (pinfunction "AGND_2_9") (pintype "passive"))
      (node (ref "J1") (pin "5") (pinfunction "5_5") (pintype "passive"))
      (node (ref "J1") (pin "MH1") (pinfunction "MH1_MH1") (pintype "passive"))
      (node (ref "J1") (pin "MH2") (pinfunction "MH2_MH2") (pintype "passive"))
      (node (ref "J1") (pin "MH3") (pinfunction "MH3_MH3") (pintype "passive"))
      (node (ref "J1") (pin "MH4") (pinfunction "MH4_MH4") (pintype "passive"))
      (node (ref "L7") (pin "2") (pinfunction "2_2") (pintype "passive"))
      (node (ref "L8") (pin "2") (pinfunction "2_2") (pintype "passive"))
      (node (ref "P1") (pin "20") (pinfunction "20_20") (pintype "passive"))
      (node (ref "P1") (pin "25") (pinfunction "25_25") (pintype "passive"))
      (node (ref "P1") (pin "30") (pinfunction "30_30") (pintype "passive"))
      (node (ref "P1") (pin "34") (pinfunction "34_34") (pintype "passive"))
      (node (ref "P1") (pin "39") (pinfunction "39_39") (pintype "passive"))
      (node (ref "P1") (pin "6") (pinfunction "6_6") (pintype "passive"))
      (node (ref "P1") (pin "9") (pinfunction "9_9") (pintype "passive"))
      (node (ref "R9") (pin "2") (pinfunction "2_2") (pintype "passive"))
      (node (ref "U1") (pin "1") (pinfunction "adj/gnd_1") (pintype "passive"))
      (node (ref "U3") (pin "5") (pinfunction "~{LDAC}_5") (pintype "passive"))
      (node (ref "U3") (pin "7") (pinfunction "VSS_7") (pintype "passive"))
      (node (ref "U3") (pin "9") (pinfunction "EP_9") (pintype "passive"))
    )
    (net (code "33") (name "HGND") (class "Default")
      (node (ref "C20") (pin "2") (pinfunction "2_2") (pintype "passive"))
      (node (ref "C22") (pin "1") (pinfunction "1_1") (pintype "passive"))
      (node (ref "C23") (pin "1") (pinfunction "1_1") (pintype "passive"))
      (node (ref "C24") (pin "1") (pinfunction "1_1") (pintype "passive"))
      (node (ref "C25") (pin "1") (pinfunction "1_1") (pintype "passive"))
      (node (ref "C26") (pin "1") (pinfunction "1_1") (pintype "passive"))
      (node (ref "C28") (pin "1") (pinfunction "1_1") (pintype "passive"))
      (node (ref "C29") (pin "1") (pinfunction "1_1") (pintype "passive"))
      (node (ref "C30") (pin "1") (pinfunction "1_1") (pintype "passive"))
      (node (ref "C31") (pin "1") (pinfunction "1_1") (pintype "passive"))
      (node (ref "C32") (pin "1") (pinfunction "1_1") (pintype "passive"))
      (node (ref "C33") (pin "1") (pinfunction "1_1") (pintype "passive"))
      (node (ref "C35") (pin "1") (pinfunction "1_1") (pintype "passive"))
      (node (ref "C36") (pin "2") (pinfunction "2_2") (pintype "passive"))
      (node (ref "C38") (pin "2") (pinfunction "2_2") (pintype "passive"))
      (node (ref "C39") (pin "1") (pinfunction "1_1") (pintype "passive"))
      (node (ref "C40") (pin "2") (pinfunction "2_2") (pintype "passive"))
      (node (ref "C41") (pin "2") (pinfunction "2_2") (pintype "passive"))
      (node (ref "C42") (pin "2") (pinfunction "2_2") (pintype "passive"))
      (node (ref "C43") (pin "2") (pinfunction "2_2") (pintype "passive"))
      (node (ref "C44") (pin "2") (pinfunction "2_2") (pintype "passive"))
      (node (ref "C45") (pin "2") (pinfunction "2_2") (pintype "passive"))
      (node (ref "C46") (pin "2") (pinfunction "2_2") (pintype "passive"))
      (node (ref "C48") (pin "2") (pinfunction "2_2") (pintype "passive"))
      (node (ref "D2") (pin "1") (pinfunction "K_1") (pintype "passive"))
      (node (ref "L6") (pin "1") (pinfunction "1_1") (pintype "passive"))
      (node (ref "L7") (pin "1") (pinfunction "1_1") (pintype "passive"))
      (node (ref "L8") (pin "1") (pinfunction "1_1") (pintype "passive"))
      (node (ref "R11") (pin "1") (pinfunction "1_1") (pintype "passive"))
      (node (ref "R14") (pin "1") (pinfunction "1_1") (pintype "passive"))
      (node (ref "R17") (pin "2") (pinfunction "2_2") (pintype "passive"))
      (node (ref "R18") (pin "1") (pinfunction "1_1") (pintype "passive"))
      (node (ref "R20") (pin "1") (pintype "passive"))
      (node (ref "R22") (pin "1") (pinfunction "1_1") (pintype "passive"))
      (node (ref "U2") (pin "4") (pinfunction "AGND_4") (pintype "passive"))
      (node (ref "U2") (pin "5") (pinfunction "DGND_5") (pintype "passive"))
    )
    (net (code "34") (name "Net-(C21-Pad1)") (class "Default")
      (node (ref "C21") (pin "1") (pinfunction "1_1") (pintype "passive"))
      (node (ref "C34") (pin "1") (pinfunction "1_1") (pintype "passive"))
      (node (ref "L4") (pin "2") (pinfunction "2_2") (pintype "passive"))
      (node (ref "Q2") (pin "5") (pinfunction "D_5") (pintype "passive"))
      (node (ref "Q2") (pin "6") (pinfunction "D_6") (pintype "passive"))
      (node (ref "Q2") (pin "7") (pinfunction "D_7") (pintype "passive"))
      (node (ref "Q2") (pin "8") (pinfunction "D_8") (pintype "passive"))
      (node (ref "Q2") (pin "9") (pinfunction "D_9") (pintype "passive"))
    )
    (net (code "35") (name "Net-(C37-Pad2)") (class "Default")
      (node (ref "C37") (pin "2") (pinfunction "2_2") (pintype "passive"))
      (node (ref "R18") (pin "2") (pinfunction "2_2") (pintype "passive"))
    )
    (net (code "36") (name "Net-(C41-Pad1)") (class "Default")
      (node (ref "C41") (pin "1") (pinfunction "1_1") (pintype "passive"))
      (node (ref "C42") (pin "1") (pinfunction "1_1") (pintype "passive"))
      (node (ref "C43") (pin "1") (pinfunction "1_1") (pintype "passive"))
      (node (ref "C44") (pin "1") (pinfunction "1_1") (pintype "passive"))
      (node (ref "L10") (pin "1") (pinfunction "1_1") (pintype "passive"))
      (node (ref "L9") (pin "1") (pinfunction "1_1") (pintype "passive"))
      (node (ref "R17") (pin "1") (pinfunction "1_1") (pintype "passive"))
    )
    (net (code "37") (name "Net-(D1-A)") (class "Default")
      (node (ref "C21") (pin "2") (pinfunction "2_2") (pintype "passive"))
      (node (ref "D1") (pin "2") (pinfunction "A_2") (pintype "passive"))
      (node (ref "L6") (pin "2") (pinfunction "2_2") (pintype "passive"))
    )
    (net (code "38") (name "Net-(D1-K)") (class "Default")
      (node (ref "C28") (pin "2") (pinfunction "2_2") (pintype "passive"))
      (node (ref "C29") (pin "2") (pinfunction "2_2") (pintype "passive"))
      (node (ref "C30") (pin "2") (pinfunction "2_2") (pintype "passive"))
      (node (ref "C31") (pin "2") (pinfunction "2_2") (pintype "passive"))
      (node (ref "D1") (pin "1") (pinfunction "K_1") (pintype "passive"))
      (node (ref "L5") (pin "1") (pinfunction "1_1") (pintype "passive"))
      (node (ref "R14") (pin "2") (pinfunction "2_2") (pintype "passive"))
    )
    (net (code "39") (name "Net-(D2-A)") (class "Default")
      (node (ref "C34") (pin "2") (pinfunction "2_2") (pintype "passive"))
      (node (ref "D2") (pin "2") (pinfunction "A_2") (pintype "passive"))
      (node (ref "L9") (pin "2") (pinfunction "2_2") (pintype "passive"))
    )
    (net (code "40") (name "Net-(D3-A)") (class "Default")
      (node (ref "D3") (pin "2") (pinfunction "A_2") (pintype "passive"))
      (node (ref "Q2") (pin "4") (pinfunction "G_4") (pintype "passive"))
      (node (ref "R16") (pin "2") (pinfunction "2_2") (pintype "passive"))
    )
    (net (code "41") (name "Net-(D3-K)") (class "Default")
      (node (ref "D3") (pin "1") (pinfunction "K_1") (pintype "passive"))
      (node (ref "R16") (pin "1") (pinfunction "1_1") (pintype "passive"))
      (node (ref "U2") (pin "6") (pinfunction "DR_6") (pintype "passive"))
    )
    (net (code "42") (name "Net-(P1-Pad7)") (class "Default")
      (node (ref "P1") (pin "7") (pinfunction "7_7") (pintype "passive"))
      (node (ref "R1") (pin "2") (pinfunction "2_2") (pintype "passive"))
    )
    (net (code "43") (name "Net-(P1-Pad8)") (class "Default")
      (node (ref "P1") (pin "8") (pinfunction "8_8") (pintype "passive"))
      (node (ref "R2") (pin "1") (pinfunction "1_1") (pintype "passive"))
    )
    (net (code "44") (name "Net-(P1-Pad10)") (class "Default")
      (node (ref "P1") (pin "10") (pinfunction "10_10") (pintype "passive"))
      (node (ref "R3") (pin "1") (pinfunction "1_1") (pintype "passive"))
    )
    (net (code "45") (name "Net-(P1-Pad26)") (class "Default")
      (node (ref "P1") (pin "26") (pinfunction "26_26") (pintype "passive"))
      (node (ref "R4") (pin "1") (pinfunction "1_1") (pintype "passive"))
    )
    (net (code "46") (name "Net-(P1-Pad29)") (class "Default")
      (node (ref "P1") (pin "29") (pinfunction "29_29") (pintype "passive"))
      (node (ref "R5") (pin "2") (pinfunction "2_2") (pintype "passive"))
    )
    (net (code "47") (name "Net-(P1-Pad37)") (class "Default")
      (node (ref "P1") (pin "37") (pinfunction "37_37") (pintype "passive"))
      (node (ref "R6") (pin "2") (pinfunction "2_2") (pintype "passive"))
    )
    (net (code "48") (name "Net-(P1-Pad40)") (class "Default")
      (node (ref "P1") (pin "40") (pinfunction "40_40") (pintype "passive"))
      (node (ref "R7") (pin "1") (pinfunction "1_1") (pintype "passive"))
    )
    (net (code "49") (name "Net-(Q1-B)") (class "Default")
      (node (ref "C26") (pin "2") (pinfunction "2_2") (pintype "passive"))
      (node (ref "Q1") (pin "1") (pinfunction "B_1") (pintype "passive"))
      (node (ref "R12") (pin "2") (pinfunction "2_2") (pintype "passive"))
    )
    (net (code "50") (name "Net-(Q1-E)") (class "Default")
      (node (ref "L3") (pin "1") (pinfunction "1_1") (pintype "passive"))
      (node (ref "Q1") (pin "2") (pinfunction "E_2") (pintype "passive"))
    )
    (net (code "51") (name "Net-(Q3-B)") (class "Default")
      (node (ref "C40") (pin "1") (pinfunction "1_1") (pintype "passive"))
      (node (ref "Q3") (pin "1") (pinfunction "B_1") (pintype "passive"))
      (node (ref "R19") (pin "2") (pinfunction "2_2") (pintype "passive"))
    )
    (net (code "52") (name "Net-(Q3-C)") (class "Default")
      (node (ref "C45") (pin "1") (pinfunction "1_1") (pintype "passive"))
      (node (ref "C46") (pin "1") (pinfunction "1_1") (pintype "passive"))
      (node (ref "L10") (pin "2") (pinfunction "2_2") (pintype "passive"))
      (node (ref "Q3") (pin "3") (pinfunction "C_3") (pintype "passive"))
      (node (ref "R19") (pin "1") (pinfunction "1_1") (pintype "passive"))
    )
    (net (code "53") (name "Net-(Q3-E)") (class "Default")
      (node (ref "L11") (pin "1") (pinfunction "1_1") (pintype "passive"))
      (node (ref "Q3") (pin "2") (pinfunction "E_2") (pintype "passive"))
    )
    (net (code "54") (name "Net-(U1-vout)") (class "Default")
      (node (ref "C18") (pin "2") (pinfunction "2_2") (pintype "passive"))
      (node (ref "F2") (pin "1") (pinfunction "1_1") (pintype "passive"))
      (node (ref "U1") (pin "2") (pinfunction "vout_2") (pintype "passive"))
    )
    (net (code "55") (name "Net-(U2-COMP)") (class "Default")
      (node (ref "C37") (pin "1") (pinfunction "1_1") (pintype "passive"))
      (node (ref "C38") (pin "1") (pinfunction "1_1") (pintype "passive"))
      (node (ref "U2") (pin "2") (pinfunction "COMP_2") (pintype "passive"))
    )
    (net (code "56") (name "Net-(U2-FA{slash}SD)") (class "Default")
      (node (ref "C20") (pin "1") (pinfunction "1_1") (pintype "passive"))
      (node (ref "R10") (pin "2") (pinfunction "2_2") (pintype "passive"))
      (node (ref "R11") (pin "2") (pinfunction "2_2") (pintype "passive"))
      (node (ref "U2") (pin "7") (pinfunction "FA/SD_7") (pintype "passive"))
    )
    (net (code "57") (name "Net-(U2-FB)") (class "Default")
      (node (ref "C48") (pin "1") (pinfunction "1_1") (pintype "passive"))
      (node (ref "R21") (pin "2") (pinfunction "2_2") (pintype "passive"))
      (node (ref "R22") (pin "2") (pinfunction "2_2") (pintype "passive"))
      (node (ref "R23") (pin "2") (pinfunction "2_2") (pintype "passive"))
      (node (ref "U2") (pin "3") (pinfunction "FB_3") (pintype "passive"))
    )
    (net (code "58") (name "Net-(U2-ISEN)") (class "Default")
      (node (ref "C36") (pin "1") (pinfunction "1_1") (pintype "passive"))
      (node (ref "R15") (pin "1") (pinfunction "1_1") (pintype "passive"))
      (node (ref "U2") (pin "1") (pinfunction "ISEN_1") (pintype "passive"))
    )
    (net (code "59") (name "Net-(U2-VIN)") (class "Default")
      (node (ref "C25") (pin "2") (pinfunction "2_2") (pintype "passive"))
      (node (ref "R13") (pin "1") (pinfunction "1_1") (pintype "passive"))
      (node (ref "U2") (pin "8") (pinfunction "VIN_8") (pintype "passive"))
    )
    (net (code "60") (name "Net-(U3-VOUT)") (class "Default")
      (node (ref "R23") (pin "1") (pinfunction "1_1") (pintype "passive"))
      (node (ref "U3") (pin "8") (pinfunction "VOUT_8") (pintype "passive"))
    )
    (net (code "61") (name "unconnected-(IC1-ACBUS1-Pad25)") (class "Default")
      (node (ref "IC1") (pin "25") (pinfunction "ACBUS1_25") (pintype "passive"))
    )
    (net (code "62") (name "unconnected-(IC1-ACBUS2-Pad26)") (class "Default")
      (node (ref "IC1") (pin "26") (pinfunction "ACBUS2_26") (pintype "passive"))
    )
    (net (code "63") (name "unconnected-(IC1-ACBUS3-Pad27)") (class "Default")
      (node (ref "IC1") (pin "27") (pinfunction "ACBUS3_27") (pintype "passive"))
    )
    (net (code "64") (name "unconnected-(IC1-ACBUS4-Pad28)") (class "Default")
      (node (ref "IC1") (pin "28") (pinfunction "ACBUS4_28") (pintype "passive"))
    )
    (net (code "65") (name "unconnected-(IC1-ACBUS5-Pad29)") (class "Default")
      (node (ref "IC1") (pin "29") (pinfunction "ACBUS5_29") (pintype "passive"))
    )
    (net (code "66") (name "unconnected-(IC1-ACBUS6-Pad30)") (class "Default")
      (node (ref "IC1") (pin "30") (pinfunction "ACBUS6_30") (pintype "passive"))
    )
    (net (code "67") (name "unconnected-(IC1-EECLK-Pad44)") (class "Default")
      (node (ref "IC1") (pin "44") (pinfunction "EECLK_44") (pintype "passive"))
    )
    (net (code "68") (name "unconnected-(IC1-EECS-Pad45)") (class "Default")
      (node (ref "IC1") (pin "45") (pinfunction "EECS_45") (pintype "passive"))
    )
    (net (code "69") (name "unconnected-(IC1-EEDATA-Pad43)") (class "Default")
      (node (ref "IC1") (pin "43") (pinfunction "EEDATA_43") (pintype "passive"))
    )
    (net (code "70") (name "unconnected-(J1-Pad4)") (class "Default")
      (node (ref "J1") (pin "4") (pinfunction "4_4") (pintype "passive"))
    )
    (net (code "71") (name "unconnected-(K1-Pad1)") (class "Default")
      (node (ref "K1") (pin "1") (pinfunction "1_1") (pintype "passive"))
    )
    (net (code "72") (name "unconnected-(K2-Pad1)") (class "Default")
      (node (ref "K2") (pin "1") (pinfunction "1_1") (pintype "passive"))
    )
    (net (code "73") (name "unconnected-(P1-Pad3)") (class "Default")
      (node (ref "P1") (pin "3") (pinfunction "3_3") (pintype "passive"))
    )
    (net (code "74") (name "unconnected-(P1-Pad5)") (class "Default")
      (node (ref "P1") (pin "5") (pinfunction "5_5") (pintype "passive"))
    )
    (net (code "75") (name "unconnected-(P1-Pad11)") (class "Default")
      (node (ref "P1") (pin "11") (pinfunction "11_11") (pintype "passive"))
    )
    (net (code "76") (name "unconnected-(P1-Pad12)") (class "Default")
      (node (ref "P1") (pin "12") (pinfunction "12_12") (pintype "passive"))
    )
    (net (code "77") (name "unconnected-(P1-Pad13)") (class "Default")
      (node (ref "P1") (pin "13") (pinfunction "13_13") (pintype "passive"))
    )
    (net (code "78") (name "unconnected-(P1-Pad14)") (class "Default")
      (node (ref "P1") (pin "14") (pinfunction "14_14") (pintype "passive"))
    )
    (net (code "79") (name "unconnected-(P1-Pad15)") (class "Default")
      (node (ref "P1") (pin "15") (pinfunction "15_15") (pintype "passive"))
    )
    (net (code "80") (name "unconnected-(P1-Pad16)") (class "Default")
      (node (ref "P1") (pin "16") (pinfunction "16_16") (pintype "passive"))
    )
    (net (code "81") (name "unconnected-(P1-Pad17)") (class "Default")
      (node (ref "P1") (pin "17") (pinfunction "17_17") (pintype "passive"))
    )
    (net (code "82") (name "unconnected-(P1-Pad18)") (class "Default")
      (node (ref "P1") (pin "18") (pinfunction "18_18") (pintype "passive"))
    )
    (net (code "83") (name "unconnected-(P1-Pad22)") (class "Default")
      (node (ref "P1") (pin "22") (pinfunction "22_22") (pintype "passive"))
    )
    (net (code "84") (name "unconnected-(P1-Pad27)") (class "Default")
      (node (ref "P1") (pin "27") (pinfunction "27_27") (pintype "passive"))
    )
    (net (code "85") (name "unconnected-(P1-Pad28)") (class "Default")
      (node (ref "P1") (pin "28") (pinfunction "28_28") (pintype "passive"))
    )
    (net (code "86") (name "unconnected-(P1-Pad31)") (class "Default")
      (node (ref "P1") (pin "31") (pinfunction "31_31") (pintype "passive"))
    )
    (net (code "87") (name "unconnected-(P1-Pad32)") (class "Default")
      (node (ref "P1") (pin "32") (pinfunction "32_32") (pintype "passive"))
    )
    (net (code "88") (name "unconnected-(P1-Pad33)") (class "Default")
      (node (ref "P1") (pin "33") (pinfunction "33_33") (pintype "passive"))
    )
    (net (code "89") (name "unconnected-(P1-Pad35)") (class "Default")
      (node (ref "P1") (pin "35") (pinfunction "35_35") (pintype "passive"))
    )
    (net (code "90") (name "unconnected-(P1-Pad36)") (class "Default")
      (node (ref "P1") (pin "36") (pinfunction "36_36") (pintype "passive"))
    )
    (net (code "91") (name "unconnected-(P1-Pad38)") (class "Default")
      (node (ref "P1") (pin "38") (pinfunction "38_38") (pintype "passive"))
    )
    (net (code "92") (name "unconnected-(Y1-GND_1-Pad2)") (class "Default")
      (node (ref "Y1") (pin "2") (pinfunction "GND_1_2") (pintype "passive"))
    )
    (net (code "93") (name "unconnected-(Y1-GND_2-Pad4)") (class "Default")
      (node (ref "Y1") (pin "4") (pinfunction "GND_2_4") (pintype "passive"))
    )
  )
)
